# growth_pcb.net
KiCad netlist of a schematic drawn in EAGLE
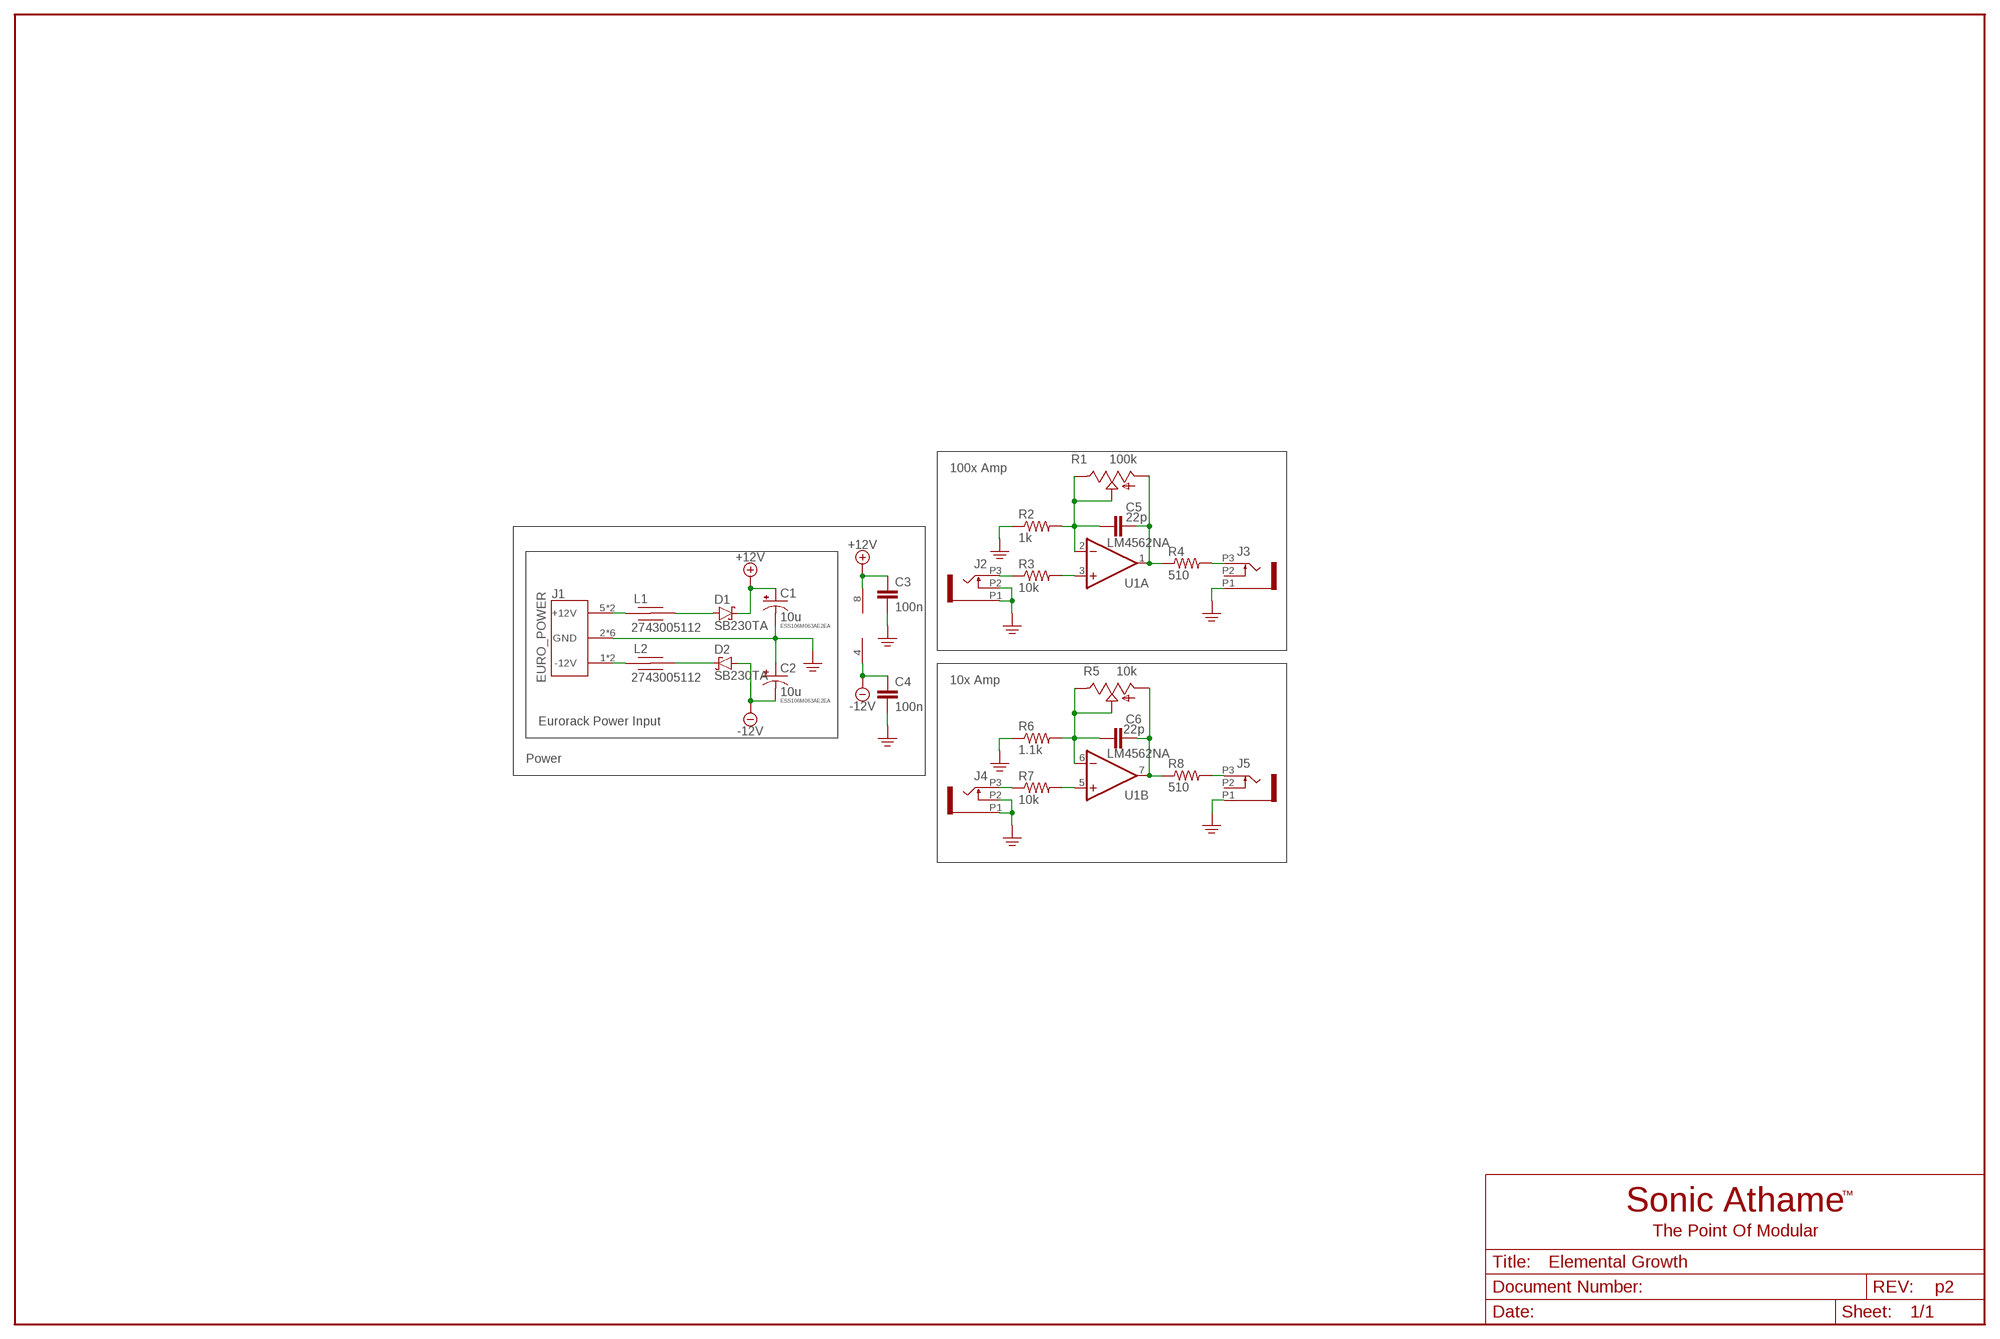
[diagram p0: schematic, sheet 1]

(export (version "E")
  (design (tool "Eeschema 10.0.6"))
  (components
    (comp (ref "C1")
      (value "10u")
      (footprint "eagle-import:TT2D5")
      (libsource (lib "eagle-import") (part "CAP_POLLYTIC_V"))
    )
    (comp (ref "C2")
      (value "10u")
      (footprint "eagle-import:TT2D5")
      (libsource (lib "eagle-import") (part "CAP_POLLYTIC_V"))
    )
    (comp (ref "C3")
      (value "100n")
      (footprint "eagle-import:C025-024X044")
      (libsource (lib "eagle-import") (part "CAP_NONPOL025-024X044"))
    )
    (comp (ref "C4")
      (value "100n")
      (footprint "eagle-import:C025-024X044")
      (libsource (lib "eagle-import") (part "CAP_NONPOL025-024X044"))
    )
    (comp (ref "C5")
      (value "22p")
      (footprint "eagle-import:C025-024X044")
      (libsource (lib "eagle-import") (part "CAP_NONPOL025-024X044"))
    )
    (comp (ref "C6")
      (value "22p")
      (footprint "eagle-import:C025-024X044")
      (libsource (lib "eagle-import") (part "CAP_NONPOL025-024X044"))
    )
    (comp (ref "D1")
      (value "SB230TA")
      (footprint "eagle-import:0207_2V-POL")
      (libsource (lib "eagle-import") (part "SCHOTTKY_THT"))
    )
    (comp (ref "D2")
      (value "SB230TA")
      (footprint "eagle-import:0207_2V-POL")
      (libsource (lib "eagle-import") (part "SCHOTTKY_THT"))
    )
    (comp (ref "J1")
      (value "EURO_POWER")
      (footprint "eagle-import:EURO_POWER")
      (libsource (lib "eagle-import") (part "EURO_POWER"))
    )
    (comp (ref "J2")
      (value "WQP-PJ398SM6")
      (footprint "eagle-import:WQP_PJ_301M6")
      (libsource (lib "eagle-import") (part "WQP-PJ398SM6"))
    )
    (comp (ref "J3")
      (value "WQP-PJ398SM6")
      (footprint "eagle-import:WQP_PJ_301M6")
      (libsource (lib "eagle-import") (part "WQP-PJ398SM6"))
    )
    (comp (ref "J4")
      (value "WQP-PJ398SM6")
      (footprint "eagle-import:WQP_PJ_301M6")
      (libsource (lib "eagle-import") (part "WQP-PJ398SM6"))
    )
    (comp (ref "J5")
      (value "WQP-PJ398SM6")
      (footprint "eagle-import:WQP_PJ_301M6")
      (libsource (lib "eagle-import") (part "WQP-PJ398SM6"))
    )
    (comp (ref "L1")
      (value "2743005112")
      (footprint "eagle-import:0207_2V")
      (libsource (lib "eagle-import") (part "FERRITE_THT"))
    )
    (comp (ref "L2")
      (value "2743005112")
      (footprint "eagle-import:0207_2V")
      (libsource (lib "eagle-import") (part "FERRITE_THT"))
    )
    (comp (ref "R1")
      (value "100k")
      (footprint "eagle-import:ALPHA_POT_VERTICAL")
      (libsource (lib "eagle-import") (part "ALPHA_POT_VERTICALVERTICAL"))
    )
    (comp (ref "R2")
      (value "1k")
      (footprint "eagle-import:0207_2V")
      (libsource (lib "eagle-import") (part "RESISTOR0207/2V"))
    )
    (comp (ref "R3")
      (value "10k")
      (footprint "eagle-import:0207_2V")
      (libsource (lib "eagle-import") (part "RESISTOR0207/2V"))
    )
    (comp (ref "R4")
      (value "510")
      (footprint "eagle-import:0207_2V")
      (libsource (lib "eagle-import") (part "RESISTOR0207/2V"))
    )
    (comp (ref "R5")
      (value "10k")
      (footprint "eagle-import:ALPHA_POT_VERTICAL")
      (libsource (lib "eagle-import") (part "ALPHA_POT_VERTICALVERTICAL"))
    )
    (comp (ref "R6")
      (value "1.1k")
      (footprint "eagle-import:0207_2V")
      (libsource (lib "eagle-import") (part "RESISTOR0207/2V"))
    )
    (comp (ref "R7")
      (value "10k")
      (footprint "eagle-import:0207_2V")
      (libsource (lib "eagle-import") (part "RESISTOR0207/2V"))
    )
    (comp (ref "R8")
      (value "510")
      (footprint "eagle-import:0207_2V")
      (libsource (lib "eagle-import") (part "RESISTOR0207/2V"))
    )
    (comp (ref "U1")
      (value "LM4562NA")
      (footprint "eagle-import:DIL08")
      (libsource (lib "eagle-import") (part "TL072P"))
    )
  )
  (nets
    (net (code "1") (name "+12V") (class "Default")
      (node (ref "C1") (pin "+") (pinfunction "+_+") (pintype "passive"))
      (node (ref "C3") (pin "1") (pinfunction "1_1") (pintype "passive"))
      (node (ref "D1") (pin "C") (pinfunction "C_C") (pintype "passive"))
      (node (ref "U1") (pin "8") (pinfunction "V+_8") (pintype "power_in"))
    )
    (net (code "2") (name "-12V") (class "Default")
      (node (ref "C2") (pin "-") (pinfunction "-_-") (pintype "passive"))
      (node (ref "C4") (pin "1") (pinfunction "1_1") (pintype "passive"))
      (node (ref "D2") (pin "A") (pinfunction "A_A") (pintype "passive"))
      (node (ref "U1") (pin "4") (pinfunction "V-_4") (pintype "power_in"))
    )
    (net (code "3") (name "GND") (class "Default")
      (node (ref "C1") (pin "-") (pinfunction "-_-") (pintype "passive"))
      (node (ref "C2") (pin "+") (pinfunction "+_+") (pintype "passive"))
      (node (ref "C3") (pin "2") (pinfunction "2_2") (pintype "passive"))
      (node (ref "C4") (pin "2") (pinfunction "2_2") (pintype "passive"))
      (node (ref "J1") (pin "2") (pinfunction "GND_2") (pintype "bidirectional"))
      (node (ref "J1") (pin "3") (pinfunction "GND_3") (pintype "bidirectional"))
      (node (ref "J1") (pin "4") (pinfunction "GND_4") (pintype "bidirectional"))
      (node (ref "J1") (pin "7") (pinfunction "GND_7") (pintype "bidirectional"))
      (node (ref "J1") (pin "8") (pinfunction "GND_8") (pintype "bidirectional"))
      (node (ref "J1") (pin "9") (pinfunction "GND_9") (pintype "bidirectional"))
      (node (ref "J2") (pin "P1") (pinfunction "1_P1") (pintype "passive"))
      (node (ref "J2") (pin "P2") (pinfunction "2_P2") (pintype "passive"))
      (node (ref "J3") (pin "P1") (pinfunction "1_P1") (pintype "passive"))
      (node (ref "J4") (pin "P1") (pinfunction "1_P1") (pintype "passive"))
      (node (ref "J4") (pin "P2") (pinfunction "2_P2") (pintype "passive"))
      (node (ref "J5") (pin "P1") (pinfunction "1_P1") (pintype "passive"))
      (node (ref "R2") (pin "1") (pinfunction "1_1") (pintype "passive"))
      (node (ref "R6") (pin "1") (pinfunction "1_1") (pintype "passive"))
    )
    (net (code "4") (name "Net-(J2-3)") (class "Default")
      (node (ref "J2") (pin "P3") (pinfunction "3_P3") (pintype "passive"))
      (node (ref "R3") (pin "1") (pinfunction "1_1") (pintype "passive"))
    )
    (net (code "5") (name "Net-(J3-3)") (class "Default")
      (node (ref "J3") (pin "P3") (pinfunction "3_P3") (pintype "passive"))
      (node (ref "R4") (pin "2") (pinfunction "2_2") (pintype "passive"))
    )
    (net (code "6") (name "Net-(J4-3)") (class "Default")
      (node (ref "J4") (pin "P3") (pinfunction "3_P3") (pintype "passive"))
      (node (ref "R7") (pin "1") (pinfunction "1_1") (pintype "passive"))
    )
    (net (code "7") (name "Net-(J5-3)") (class "Default")
      (node (ref "J5") (pin "P3") (pinfunction "3_P3") (pintype "passive"))
      (node (ref "R8") (pin "2") (pinfunction "2_2") (pintype "passive"))
    )
    (net (code "8") (name "Net-(L1-P$1)") (class "Default")
      (node (ref "J1") (pin "5") (pinfunction "+12V_5") (pintype "bidirectional"))
      (node (ref "J1") (pin "6") (pinfunction "+12V_6") (pintype "bidirectional"))
      (node (ref "L1") (pin "1") (pinfunction "P$1_1") (pintype "bidirectional"))
    )
    (net (code "9") (name "Net-(L1-P$2)") (class "Default")
      (node (ref "D1") (pin "A") (pinfunction "A_A") (pintype "passive"))
      (node (ref "L1") (pin "2") (pinfunction "P$2_2") (pintype "bidirectional"))
    )
    (net (code "10") (name "Net-(L2-P$1)") (class "Default")
      (node (ref "J1") (pin "1") (pinfunction "-12V_1") (pintype "bidirectional"))
      (node (ref "J1") (pin "10") (pinfunction "-12V_10") (pintype "bidirectional"))
      (node (ref "L2") (pin "1") (pinfunction "P$1_1") (pintype "bidirectional"))
    )
    (net (code "11") (name "Net-(L2-P$2)") (class "Default")
      (node (ref "D2") (pin "C") (pinfunction "C_C") (pintype "passive"))
      (node (ref "L2") (pin "2") (pinfunction "P$2_2") (pintype "bidirectional"))
    )
    (net (code "12") (name "Net-(R1-A)") (class "Default")
      (node (ref "C5") (pin "2") (pinfunction "2_2") (pintype "passive"))
      (node (ref "R1") (pin "P$3") (pinfunction "A_P$3") (pintype "passive"))
      (node (ref "R4") (pin "1") (pinfunction "1_1") (pintype "passive"))
      (node (ref "U1") (pin "1") (pinfunction "OUT_1") (pintype "output"))
    )
    (net (code "13") (name "Net-(R1-E)") (class "Default")
      (node (ref "C5") (pin "1") (pinfunction "1_1") (pintype "passive"))
      (node (ref "R1") (pin "P$1") (pinfunction "E_P$1") (pintype "passive"))
      (node (ref "R1") (pin "P$2") (pinfunction "S_P$2") (pintype "passive"))
      (node (ref "R2") (pin "2") (pinfunction "2_2") (pintype "passive"))
      (node (ref "U1") (pin "2") (pinfunction "-IN_2") (pintype "input"))
    )
    (net (code "14") (name "Net-(R5-A)") (class "Default")
      (node (ref "C6") (pin "2") (pinfunction "2_2") (pintype "passive"))
      (node (ref "R5") (pin "P$3") (pinfunction "A_P$3") (pintype "passive"))
      (node (ref "R8") (pin "1") (pinfunction "1_1") (pintype "passive"))
      (node (ref "U1") (pin "7") (pinfunction "OUT_7") (pintype "output"))
    )
    (net (code "15") (name "Net-(R5-E)") (class "Default")
      (node (ref "C6") (pin "1") (pinfunction "1_1") (pintype "passive"))
      (node (ref "R5") (pin "P$1") (pinfunction "E_P$1") (pintype "passive"))
      (node (ref "R5") (pin "P$2") (pinfunction "S_P$2") (pintype "passive"))
      (node (ref "R6") (pin "2") (pinfunction "2_2") (pintype "passive"))
      (node (ref "U1") (pin "6") (pinfunction "-IN_6") (pintype "input"))
    )
    (net (code "16") (name "Net-(U1A-+IN)") (class "Default")
      (node (ref "R3") (pin "2") (pinfunction "2_2") (pintype "passive"))
      (node (ref "U1") (pin "3") (pinfunction "+IN_3") (pintype "input"))
    )
    (net (code "17") (name "Net-(U1B-+IN)") (class "Default")
      (node (ref "R7") (pin "2") (pinfunction "2_2") (pintype "passive"))
      (node (ref "U1") (pin "5") (pinfunction "+IN_5") (pintype "input"))
    )
    (net (code "18") (name "unconnected-(J3-2-PadP2)") (class "Default")
      (node (ref "J3") (pin "P2") (pinfunction "2_P2") (pintype "passive"))
    )
    (net (code "19") (name "unconnected-(J5-2-PadP2)") (class "Default")
      (node (ref "J5") (pin "P2") (pinfunction "2_P2") (pintype "passive"))
    )
  )
)
